# microrovmk2.net
KiCad netlist of a schematic drawn in EAGLE
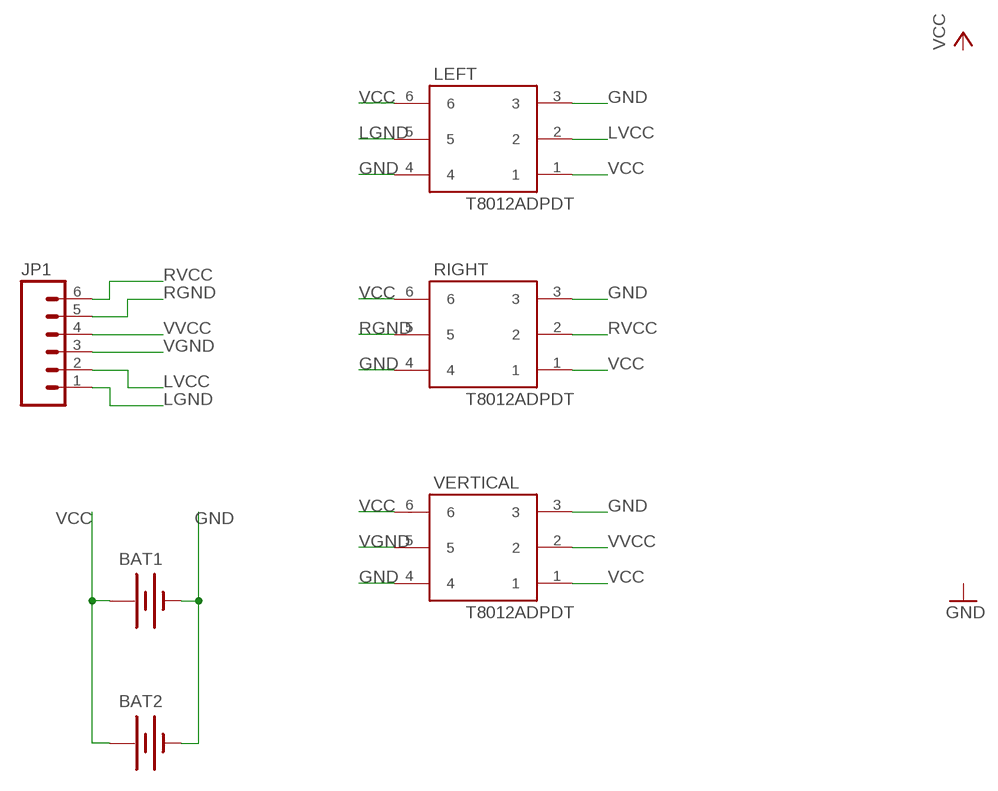
[diagram p0: schematic, sheet 1]

(export (version "E")
  (design (tool "Eeschema 10.0.6"))
  (components
    (comp (ref "BAT1")
      (value "BATTERY9V")
      (footprint "eagle-import:BATTCON_9V")
      (libsource (lib "eagle-import") (part "BATTERY9V"))
    )
    (comp (ref "BAT2")
      (value "BATTERY9V")
      (footprint "eagle-import:BATTCON_9V")
      (libsource (lib "eagle-import") (part "BATTERY9V"))
    )
    (comp (ref "JP1")
      (value "M06LOCK_LONGPADS")
      (footprint "eagle-import:1X06_LOCK_LONGPADS")
      (libsource (lib "eagle-import") (part "M06LOCK_LONGPADS"))
    )
    (comp (ref "LEFT")
      (value "T8012ADPDT")
      (footprint "eagle-import:T8012A")
      (libsource (lib "eagle-import") (part "T8012ADPDT"))
    )
    (comp (ref "RIGHT")
      (value "T8012ADPDT")
      (footprint "eagle-import:T8012A")
      (libsource (lib "eagle-import") (part "T8012ADPDT"))
    )
    (comp (ref "VERTICAL")
      (value "T8012ADPDT")
      (footprint "eagle-import:T8012A")
      (libsource (lib "eagle-import") (part "T8012ADPDT"))
    )
  )
  (nets
    (net (code "1") (name "/LGND") (class "Default")
      (node (ref "JP1") (pin "1") (pinfunction "1_1") (pintype "passive"))
      (node (ref "LEFT") (pin "5") (pinfunction "5_5") (pintype "bidirectional"))
    )
    (net (code "2") (name "/LVCC") (class "Default")
      (node (ref "JP1") (pin "2") (pinfunction "2_2") (pintype "passive"))
      (node (ref "LEFT") (pin "2") (pinfunction "2_2") (pintype "bidirectional"))
    )
    (net (code "3") (name "/RGND") (class "Default")
      (node (ref "JP1") (pin "5") (pinfunction "5_5") (pintype "passive"))
      (node (ref "RIGHT") (pin "5") (pinfunction "5_5") (pintype "bidirectional"))
    )
    (net (code "4") (name "/RVCC") (class "Default")
      (node (ref "JP1") (pin "6") (pinfunction "6_6") (pintype "passive"))
      (node (ref "RIGHT") (pin "2") (pinfunction "2_2") (pintype "bidirectional"))
    )
    (net (code "5") (name "/VGND") (class "Default")
      (node (ref "JP1") (pin "3") (pinfunction "3_3") (pintype "passive"))
      (node (ref "VERTICAL") (pin "5") (pinfunction "5_5") (pintype "bidirectional"))
    )
    (net (code "6") (name "/VVCC") (class "Default")
      (node (ref "JP1") (pin "4") (pinfunction "4_4") (pintype "passive"))
      (node (ref "VERTICAL") (pin "2") (pinfunction "2_2") (pintype "bidirectional"))
    )
    (net (code "7") (name "GND") (class "Default")
      (node (ref "BAT1") (pin "-") (pinfunction "-_-") (pintype "power_in"))
      (node (ref "BAT2") (pin "-") (pinfunction "-_-") (pintype "power_in"))
      (node (ref "LEFT") (pin "3") (pinfunction "3_3") (pintype "bidirectional"))
      (node (ref "LEFT") (pin "4") (pinfunction "4_4") (pintype "bidirectional"))
      (node (ref "RIGHT") (pin "3") (pinfunction "3_3") (pintype "bidirectional"))
      (node (ref "RIGHT") (pin "4") (pinfunction "4_4") (pintype "bidirectional"))
      (node (ref "VERTICAL") (pin "3") (pinfunction "3_3") (pintype "bidirectional"))
      (node (ref "VERTICAL") (pin "4") (pinfunction "4_4") (pintype "bidirectional"))
    )
    (net (code "8") (name "VCC") (class "Default")
      (node (ref "BAT1") (pin "+") (pinfunction "+_+") (pintype "power_in"))
      (node (ref "BAT2") (pin "+") (pinfunction "+_+") (pintype "power_in"))
      (node (ref "LEFT") (pin "1") (pinfunction "1_1") (pintype "bidirectional"))
      (node (ref "LEFT") (pin "6") (pinfunction "6_6") (pintype "bidirectional"))
      (node (ref "RIGHT") (pin "1") (pinfunction "1_1") (pintype "bidirectional"))
      (node (ref "RIGHT") (pin "6") (pinfunction "6_6") (pintype "bidirectional"))
      (node (ref "VERTICAL") (pin "1") (pinfunction "1_1") (pintype "bidirectional"))
      (node (ref "VERTICAL") (pin "6") (pinfunction "6_6") (pintype "bidirectional"))
    )
  )
)
